# Grove_Electromagnet_v1_0.net
KiCad netlist of a schematic drawn in EAGLE
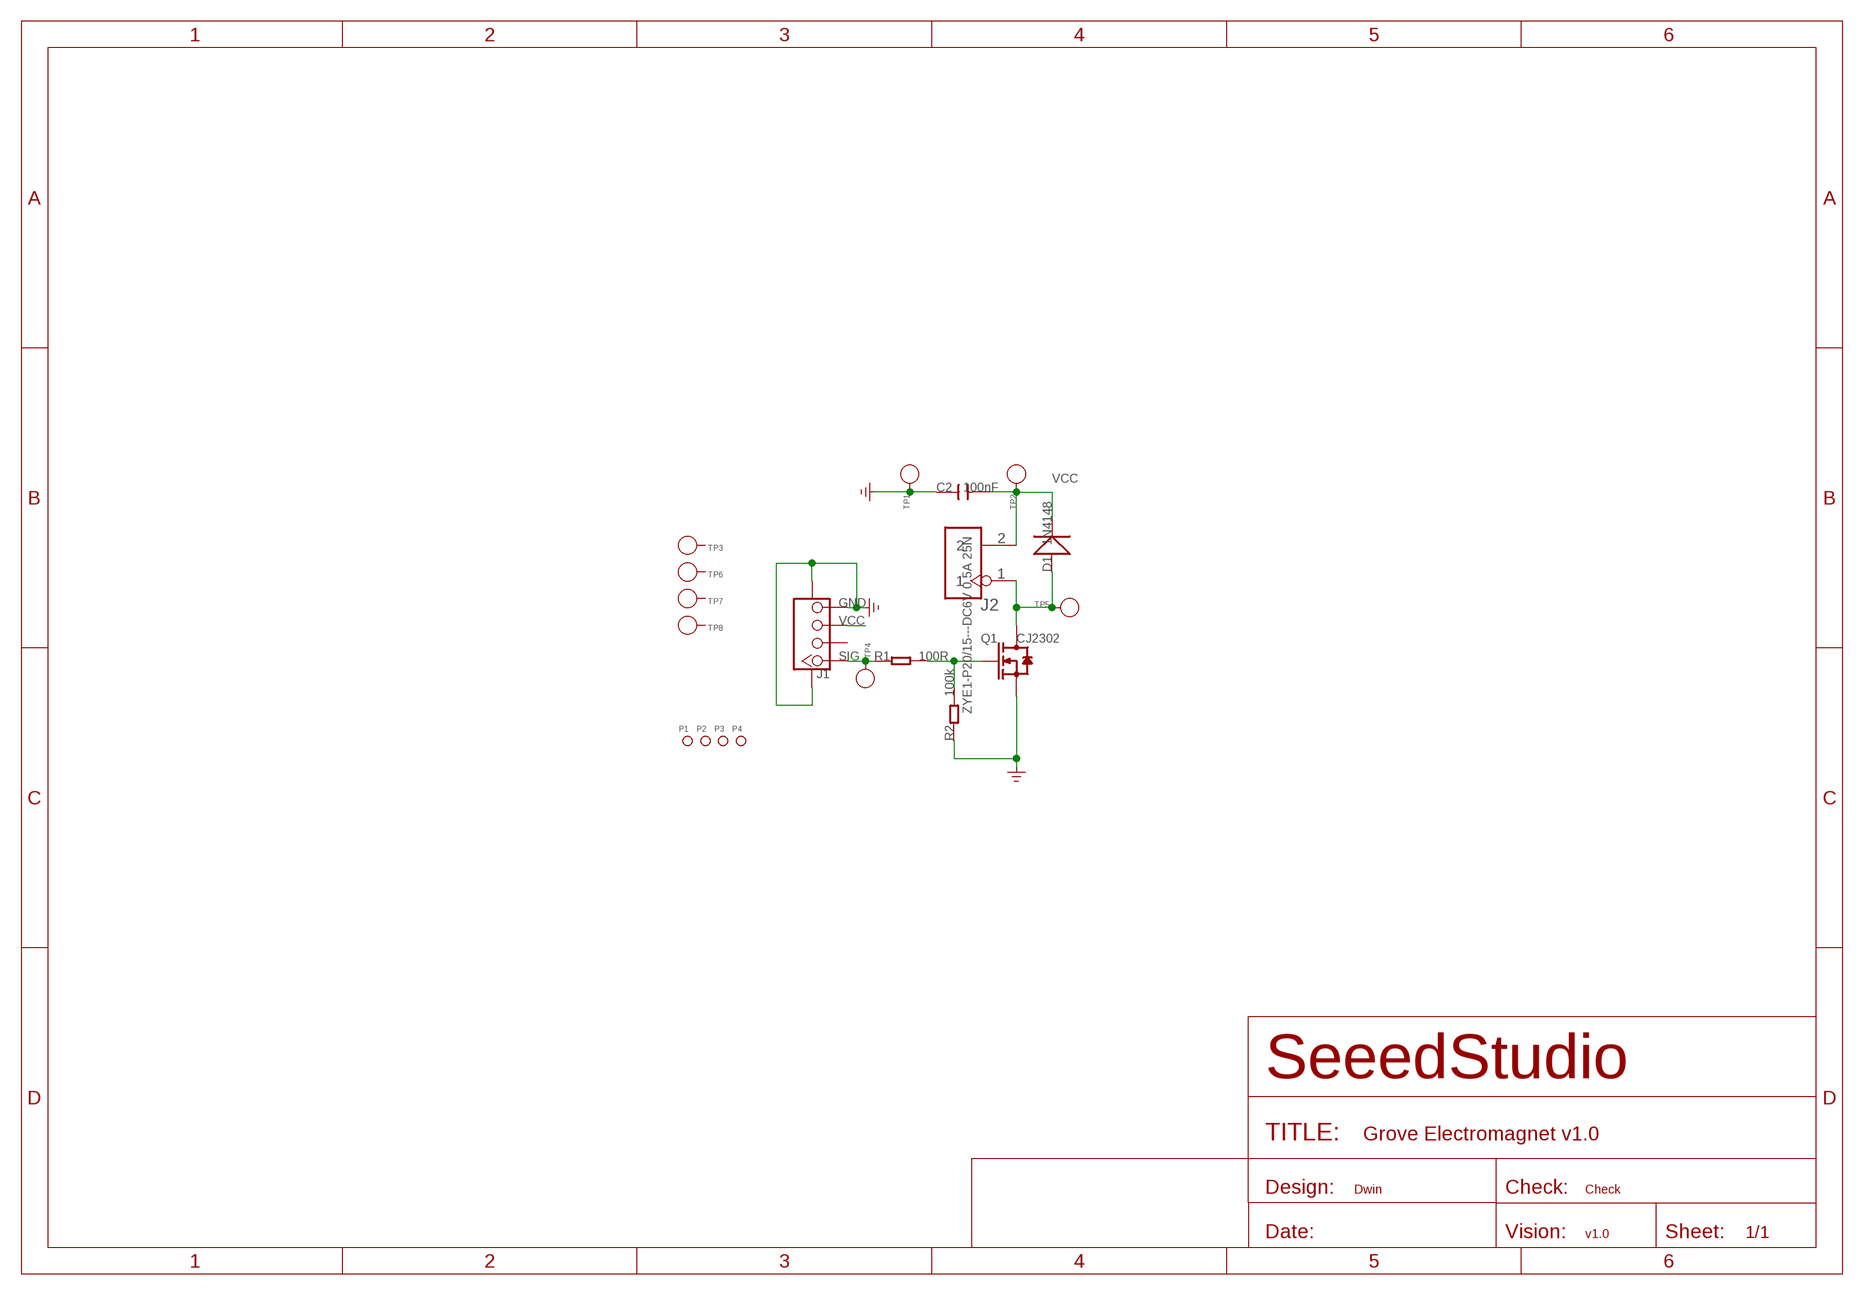
[diagram p0: schematic, sheet 1]

(export (version "E")
  (design (tool "Eeschema 10.0.6"))
  (components
    (comp (ref "C2")
      (value "100nF")
      (footprint "eagle-import:C0603")
      (libsource (lib "eagle-import") (part "C-0603"))
    )
    (comp (ref "D1")
      (value "1N4148")
      (footprint "eagle-import:LL-34")
      (libsource (lib "eagle-import") (part "D'1N4148-SMD'"))
    )
    (comp (ref "J1")
      (value "TWIG-4P-2.0-SMD-FEMALE-REINFORCE'DD'")
      (footprint "eagle-import:4P-SMD-2.0")
      (libsource (lib "eagle-import") (part "TWIG-4P-2.0-SMD-FEMALE-REINFORCE'DD'"))
    )
    (comp (ref "J2")
      (value "ZYE1-P20/15---DC6V 0.5A 25N")
      (footprint "eagle-import:2P-2.54-65_35MIL")
      (libsource (lib "eagle-import") (part "HEADER-2P-65/35MIL"))
    )
    (comp (ref "P1")
      (value "PAD-MARK")
      (footprint "eagle-import:ROUND-MARK-1.0")
      (fields (field (name "PARTNO") "DNP"))
      (libsource (lib "eagle-import") (part "PAD-MARK"))
    )
    (comp (ref "P2")
      (value "PAD-MARK")
      (footprint "eagle-import:ROUND-MARK-1.0")
      (fields (field (name "PARTNO") "DNP"))
      (libsource (lib "eagle-import") (part "PAD-MARK"))
    )
    (comp (ref "P3")
      (value "PAD-MARK")
      (footprint "eagle-import:ROUND-MARK-1.0")
      (fields (field (name "PARTNO") "DNP"))
      (libsource (lib "eagle-import") (part "PAD-MARK"))
    )
    (comp (ref "P4")
      (value "PAD-MARK")
      (footprint "eagle-import:ROUND-MARK-1.0")
      (fields (field (name "PARTNO") "DNP"))
      (libsource (lib "eagle-import") (part "PAD-MARK"))
    )
    (comp (ref "Q1")
      (value "CJ2302")
      (footprint "eagle-import:SOT23")
      (libsource (lib "eagle-import") (part "MOSFET-N'SOT23'"))
    )
    (comp (ref "R1")
      (value "100R")
      (footprint "eagle-import:R0603")
      (libsource (lib "eagle-import") (part "R-0603"))
    )
    (comp (ref "R2")
      (value "100k")
      (footprint "eagle-import:R0603")
      (libsource (lib "eagle-import") (part "R-0603"))
    )
    (comp (ref "TP1")
      (value "PAD-TEST-POINT'4545'")
      (footprint "eagle-import:TP_4545")
      (fields (field (name "PARTNO") "DNP"))
      (libsource (lib "eagle-import") (part "PAD-TEST-POINT'4545'"))
    )
    (comp (ref "TP2")
      (value "PAD-TEST-POINT'4545'")
      (footprint "eagle-import:TP_4545")
      (fields (field (name "PARTNO") "DNP"))
      (libsource (lib "eagle-import") (part "PAD-TEST-POINT'4545'"))
    )
    (comp (ref "TP3")
      (value "PAD-TEST-POINT'4545'")
      (footprint "eagle-import:TP_4545")
      (fields (field (name "PARTNO") "DNP"))
      (libsource (lib "eagle-import") (part "PAD-TEST-POINT'4545'"))
    )
    (comp (ref "TP4")
      (value "PAD-TEST-POINT'4545'")
      (footprint "eagle-import:TP_4545")
      (fields (field (name "PARTNO") "DNP"))
      (libsource (lib "eagle-import") (part "PAD-TEST-POINT'4545'"))
    )
    (comp (ref "TP5")
      (value "PAD-TEST-POINT'4545'")
      (footprint "eagle-import:TP_4545")
      (fields (field (name "PARTNO") "DNP"))
      (libsource (lib "eagle-import") (part "PAD-TEST-POINT'4545'"))
    )
    (comp (ref "TP6")
      (value "PAD-TEST-POINT'4545'")
      (footprint "eagle-import:TP_4545")
      (fields (field (name "PARTNO") "DNP"))
      (libsource (lib "eagle-import") (part "PAD-TEST-POINT'4545'"))
    )
    (comp (ref "TP7")
      (value "PAD-TEST-POINT'4545'")
      (footprint "eagle-import:TP_4545")
      (fields (field (name "PARTNO") "DNP"))
      (libsource (lib "eagle-import") (part "PAD-TEST-POINT'4545'"))
    )
    (comp (ref "TP8")
      (value "PAD-TEST-POINT'4545'")
      (footprint "eagle-import:TP_4545")
      (fields (field (name "PARTNO") "DNP"))
      (libsource (lib "eagle-import") (part "PAD-TEST-POINT'4545'"))
    )
  )
  (nets
    (net (code "1") (name "/SIG") (class "Default")
      (node (ref "J1") (pin "1") (pinfunction "1_1") (pintype "bidirectional"))
      (node (ref "R1") (pin "1") (pinfunction "1_1") (pintype "passive"))
      (node (ref "TP4") (pin "T") (pinfunction "T_T") (pintype "bidirectional"))
    )
    (net (code "2") (name "/VCC") (class "Default")
      (node (ref "C2") (pin "2") (pinfunction "2_2") (pintype "passive"))
      (node (ref "D1") (pin "C") (pinfunction "-_C") (pintype "passive"))
      (node (ref "J1") (pin "3") (pinfunction "3_3") (pintype "bidirectional"))
      (node (ref "J2") (pin "2") (pinfunction "2_2") (pintype "bidirectional"))
      (node (ref "TP2") (pin "T") (pinfunction "T_T") (pintype "bidirectional"))
    )
    (net (code "3") (name "GND_POWER") (class "Default")
      (node (ref "C2") (pin "1") (pinfunction "1_1") (pintype "passive"))
      (node (ref "J1") (pin "4") (pinfunction "4_4") (pintype "bidirectional"))
      (node (ref "J1") (pin "SS1") (pinfunction "SS1_SS1") (pintype "bidirectional"))
      (node (ref "J1") (pin "SS2") (pinfunction "SS2_SS2") (pintype "bidirectional"))
      (node (ref "Q1") (pin "2") (pinfunction "S_2") (pintype "passive"))
      (node (ref "R2") (pin "1") (pinfunction "1_1") (pintype "passive"))
      (node (ref "TP1") (pin "T") (pinfunction "T_T") (pintype "bidirectional"))
    )
    (net (code "4") (name "Net-(D1-+)") (class "Default")
      (node (ref "D1") (pin "A") (pinfunction "+_A") (pintype "passive"))
      (node (ref "J2") (pin "1") (pinfunction "1_1") (pintype "bidirectional"))
      (node (ref "Q1") (pin "3") (pinfunction "D_3") (pintype "passive"))
      (node (ref "TP5") (pin "T") (pinfunction "T_T") (pintype "bidirectional"))
    )
    (net (code "5") (name "Net-(Q1-G)") (class "Default")
      (node (ref "Q1") (pin "1") (pinfunction "G_1") (pintype "passive"))
      (node (ref "R1") (pin "2") (pinfunction "2_2") (pintype "passive"))
      (node (ref "R2") (pin "2") (pinfunction "2_2") (pintype "passive"))
    )
    (net (code "6") (name "unconnected-(J1-Pad2)") (class "Default")
      (node (ref "J1") (pin "2") (pinfunction "2_2") (pintype "bidirectional"))
    )
    (net (code "7") (name "unconnected-(TP3-PadT)") (class "Default")
      (node (ref "TP3") (pin "T") (pinfunction "T_T") (pintype "bidirectional"))
    )
    (net (code "8") (name "unconnected-(TP6-PadT)") (class "Default")
      (node (ref "TP6") (pin "T") (pinfunction "T_T") (pintype "bidirectional"))
    )
    (net (code "9") (name "unconnected-(TP7-PadT)") (class "Default")
      (node (ref "TP7") (pin "T") (pinfunction "T_T") (pintype "bidirectional"))
    )
    (net (code "10") (name "unconnected-(TP8-PadT)") (class "Default")
      (node (ref "TP8") (pin "T") (pinfunction "T_T") (pintype "bidirectional"))
    )
  )
)
